# simpleBot.net
KiCad netlist of a schematic drawn in EAGLE
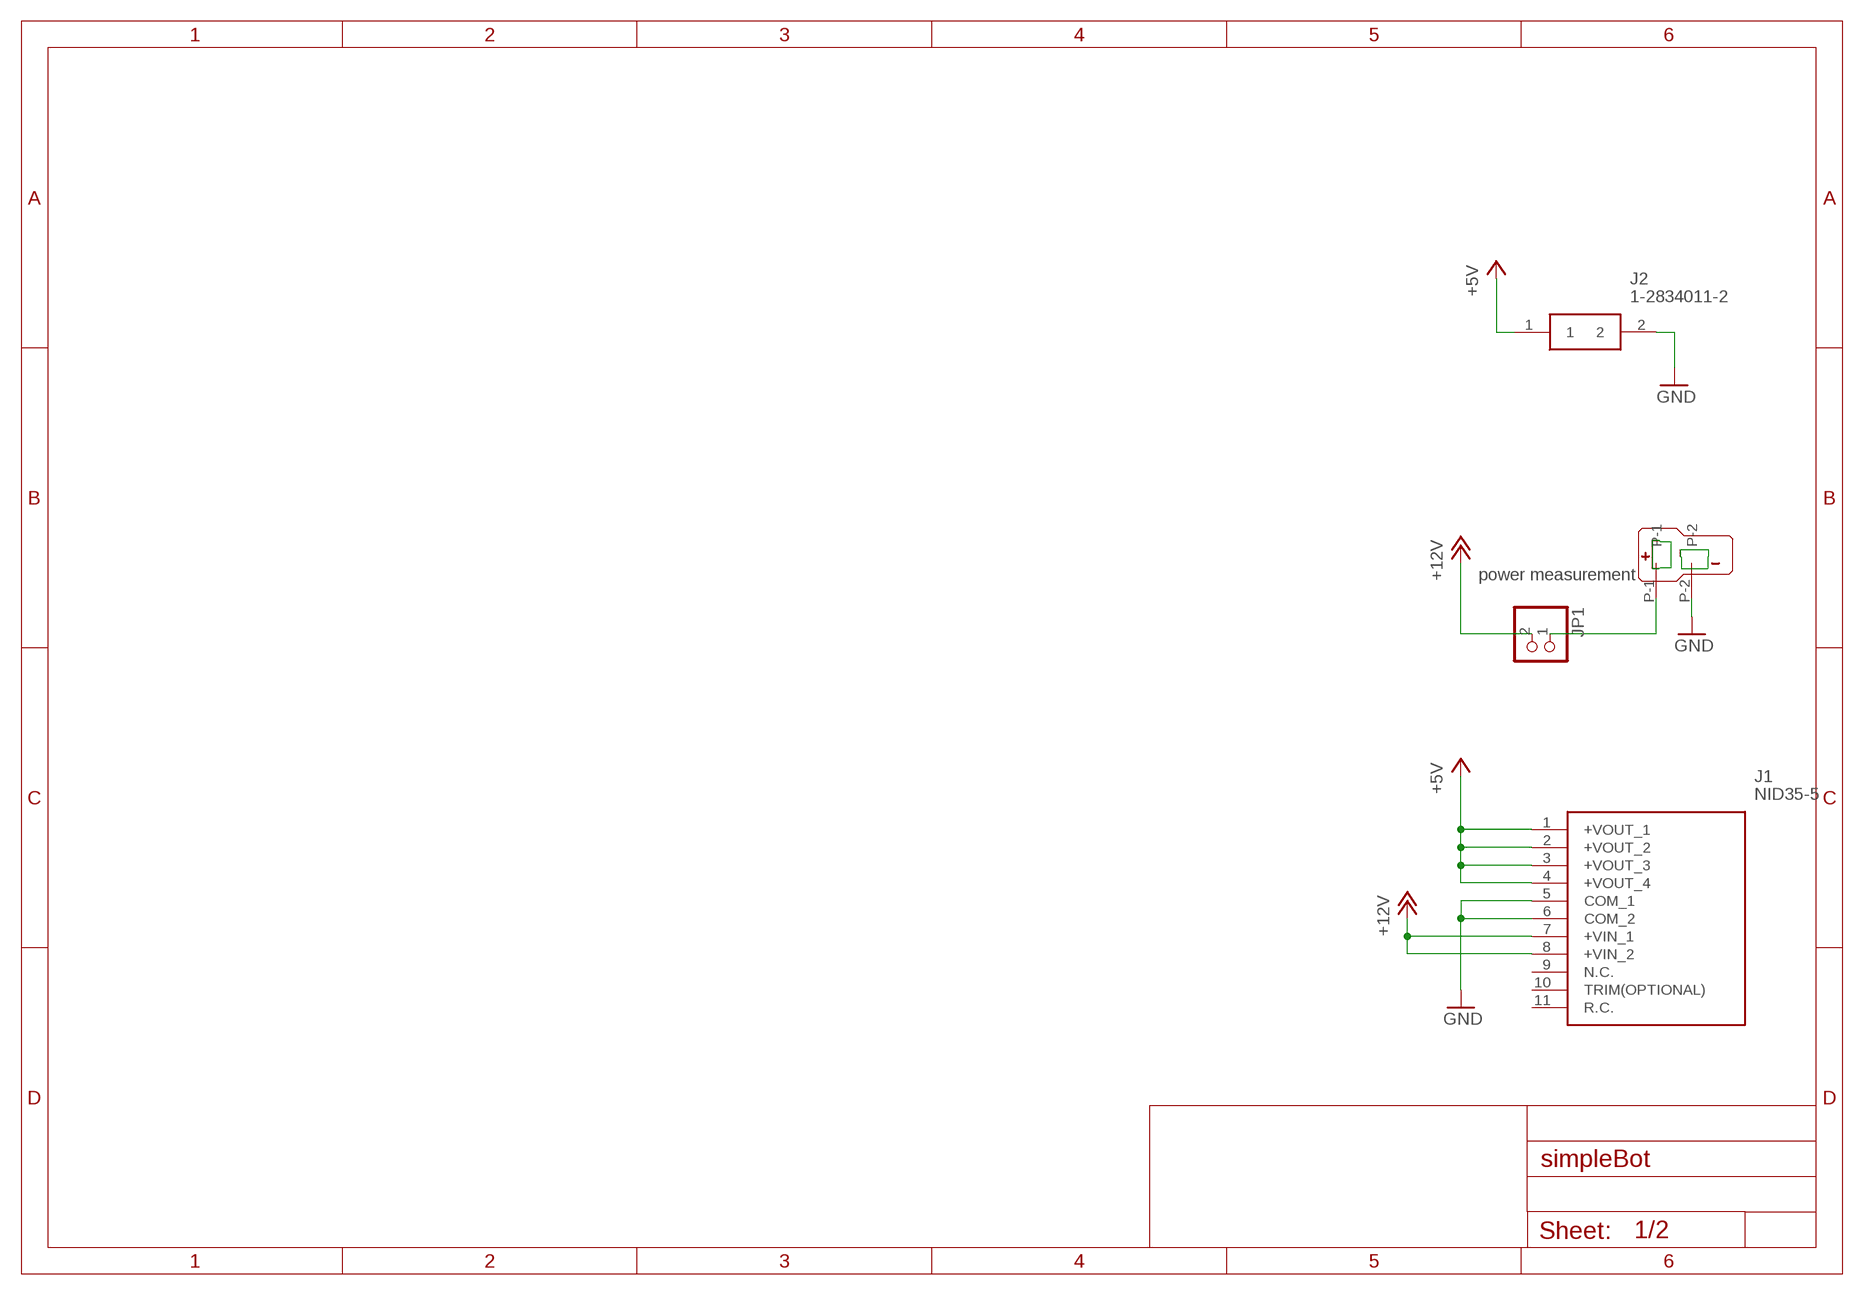
[diagram p0: schematic, sheet 1]
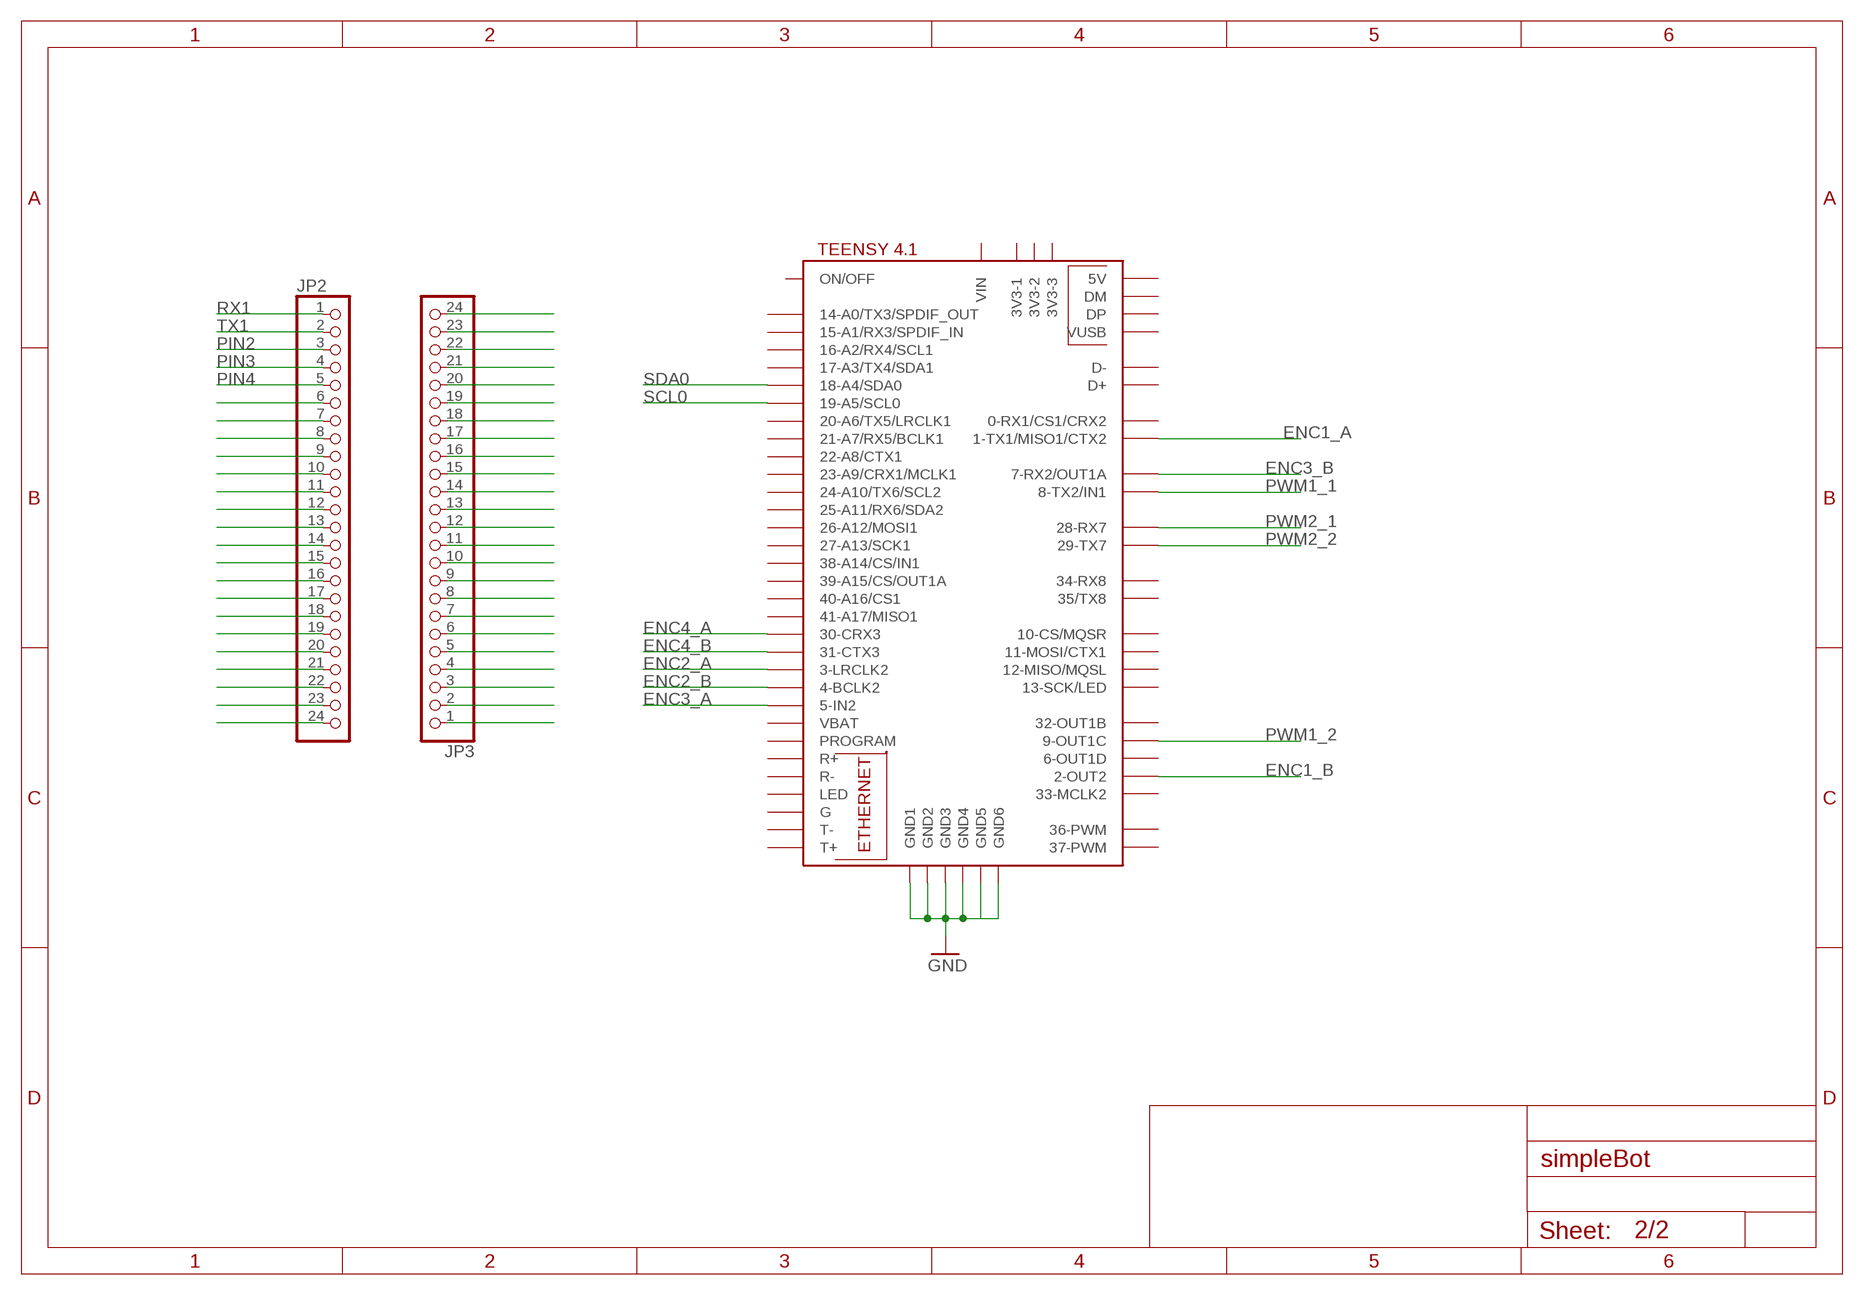
[diagram p1: schematic, sheet 2]

(export (version "E")
  (design (tool "Eeschema 10.0.6"))
  (components
    (comp (ref "JP2")
      (value "PINHD-1X24")
      (footprint "eagle-import:1X24")
      (libsource (lib "eagle-import") (part "PINHD-1X24"))
    )
    (comp (ref "JP3")
      (value "PINHD-1X24")
      (footprint "eagle-import:1X24")
      (libsource (lib "eagle-import") (part "PINHD-1X24"))
    )
    (comp (ref "U$1")
      (value "TEENSY41")
      (footprint "eagle-import:TEENSY41")
      (libsource (lib "eagle-import") (part "TEENSY41"))
    )
    (comp (ref "J1")
      (value "NID35-5")
      (footprint "eagle-import:NID355")
      (libsource (lib "eagle-import") (part "NID35-5"))
    )
    (comp (ref "J2")
      (value "1-2834011-2")
      (footprint "eagle-import:128340112")
      (fields (field (name "RS_PART_NUMBER") "1649131"))
      (libsource (lib "eagle-import") (part "1-2834011-2"))
    )
    (comp (ref "JP1")
      (value "PINHD-1X2")
      (footprint "eagle-import:1X02")
      (libsource (lib "eagle-import") (part "PINHD-1X2"))
    )
    (comp (ref "U$2")
      (value "T-PLUG_CONNECTOR")
      (footprint "eagle-import:T_PLUG_CONNECTOR")
      (libsource (lib "eagle-import") (part "T-PLUG_CONNECTOR"))
    )
  )
  (nets
    (net (code "1") (name "+5V") (class "Default")
      (node (ref "J1") (pin "1") (pinfunction "+VOUT_1_1") (pintype "bidirectional"))
      (node (ref "J1") (pin "2") (pinfunction "+VOUT_2_2") (pintype "bidirectional"))
      (node (ref "J1") (pin "3") (pinfunction "+VOUT_3_3") (pintype "bidirectional"))
      (node (ref "J1") (pin "4") (pinfunction "+VOUT_4_4") (pintype "bidirectional"))
      (node (ref "J2") (pin "1") (pinfunction "1_1") (pintype "bidirectional"))
    )
    (net (code "2") (name "+12V") (class "Default")
      (node (ref "J1") (pin "7") (pinfunction "+VIN_1_7") (pintype "bidirectional"))
      (node (ref "J1") (pin "8") (pinfunction "+VIN_2_8") (pintype "bidirectional"))
      (node (ref "JP1") (pin "2") (pinfunction "2_2") (pintype "passive"))
    )
    (net (code "3") (name "ENC1_A") (class "Default")
      (node (ref "U$1") (pin "1-TX1/MISO1/CTX2") (pinfunction "1-TX1/MISO1/CTX2_1-TX1/MISO1/CTX2") (pintype "bidirectional"))
    )
    (net (code "4") (name "ENC1_B") (class "Default")
      (node (ref "U$1") (pin "2-OUT2") (pinfunction "2-OUT2_2-OUT2") (pintype "bidirectional"))
    )
    (net (code "5") (name "ENC2_A") (class "Default")
      (node (ref "U$1") (pin "3-LRCLK2") (pinfunction "3-LRCLK2_3-LRCLK2") (pintype "bidirectional"))
    )
    (net (code "6") (name "ENC2_B") (class "Default")
      (node (ref "U$1") (pin "4-BCLK2") (pinfunction "4-BCLK2_4-BCLK2") (pintype "bidirectional"))
    )
    (net (code "7") (name "ENC3_A") (class "Default")
      (node (ref "U$1") (pin "5-IN2") (pinfunction "5-IN2_5-IN2") (pintype "bidirectional"))
    )
    (net (code "8") (name "ENC3_B") (class "Default")
      (node (ref "U$1") (pin "7-RX2/OUT1A") (pinfunction "7-RX2/OUT1A_7-RX2/OUT1A") (pintype "bidirectional"))
    )
    (net (code "9") (name "ENC4_A") (class "Default")
      (node (ref "U$1") (pin "30-CRX3") (pinfunction "30-CRX3_30-CRX3") (pintype "bidirectional"))
    )
    (net (code "10") (name "ENC4_B") (class "Default")
      (node (ref "U$1") (pin "31-CTX3") (pinfunction "31-CTX3_31-CTX3") (pintype "bidirectional"))
    )
    (net (code "11") (name "GND") (class "Default")
      (node (ref "J1") (pin "5") (pinfunction "COM_1_5") (pintype "bidirectional"))
      (node (ref "J1") (pin "6") (pinfunction "COM_2_6") (pintype "bidirectional"))
      (node (ref "J2") (pin "2") (pinfunction "2_2") (pintype "bidirectional"))
      (node (ref "U$1") (pin "GND1") (pinfunction "GND1_GND1") (pintype "bidirectional"))
      (node (ref "U$1") (pin "GND2") (pinfunction "GND2_GND2") (pintype "bidirectional"))
      (node (ref "U$1") (pin "GND3") (pinfunction "GND3_GND3") (pintype "bidirectional"))
      (node (ref "U$1") (pin "GND4") (pinfunction "GND4_GND4") (pintype "bidirectional"))
      (node (ref "U$1") (pin "GND5") (pinfunction "GND5_GND5") (pintype "bidirectional"))
      (node (ref "U$1") (pin "GND6") (pinfunction "GND6_GND6") (pintype "bidirectional"))
      (node (ref "U$2") (pin "P-2") (pinfunction "P-2_P-2") (pintype "passive"))
    )
    (net (code "12") (name "Net-(JP1-Pad1)") (class "Default")
      (node (ref "JP1") (pin "1") (pinfunction "1_1") (pintype "passive"))
      (node (ref "U$2") (pin "P-1") (pinfunction "P-1_P-1") (pintype "passive"))
    )
    (net (code "13") (name "PIN2") (class "Default")
      (node (ref "JP2") (pin "3") (pinfunction "3_3") (pintype "passive"))
    )
    (net (code "14") (name "PIN3") (class "Default")
      (node (ref "JP2") (pin "4") (pinfunction "4_4") (pintype "passive"))
    )
    (net (code "15") (name "PIN4") (class "Default")
      (node (ref "JP2") (pin "5") (pinfunction "5_5") (pintype "passive"))
    )
    (net (code "16") (name "PWM1_1") (class "Default")
      (node (ref "U$1") (pin "8-TX2/IN1") (pinfunction "8-TX2/IN1_8-TX2/IN1") (pintype "bidirectional"))
    )
    (net (code "17") (name "PWM1_2") (class "Default")
      (node (ref "U$1") (pin "9-OUT1C") (pinfunction "9-OUT1C_9-OUT1C") (pintype "bidirectional"))
    )
    (net (code "18") (name "PWM2_1") (class "Default")
      (node (ref "U$1") (pin "28-RX7") (pinfunction "28-RX7_28-RX7") (pintype "bidirectional"))
    )
    (net (code "19") (name "PWM2_2") (class "Default")
      (node (ref "U$1") (pin "29-TX7") (pinfunction "29-TX7_29-TX7") (pintype "bidirectional"))
    )
    (net (code "20") (name "RX1") (class "Default")
      (node (ref "JP2") (pin "1") (pinfunction "1_1") (pintype "passive"))
    )
    (net (code "21") (name "SCL0") (class "Default")
      (node (ref "U$1") (pin "19-A5/SCL0") (pinfunction "19-A5/SCL0_19-A5/SCL0") (pintype "bidirectional"))
    )
    (net (code "22") (name "SDA0") (class "Default")
      (node (ref "U$1") (pin "18-A4/SDA0") (pinfunction "18-A4/SDA0_18-A4/SDA0") (pintype "bidirectional"))
    )
    (net (code "23") (name "TX1") (class "Default")
      (node (ref "JP2") (pin "2") (pinfunction "2_2") (pintype "passive"))
    )
    (net (code "24") (name "unconnected-(J1-N.C.-Pad9)") (class "Default")
      (node (ref "J1") (pin "9") (pinfunction "N.C._9") (pintype "no_connect"))
    )
    (net (code "25") (name "unconnected-(J1-R.C.-Pad11)") (class "Default")
      (node (ref "J1") (pin "11") (pinfunction "R.C._11") (pintype "bidirectional"))
    )
    (net (code "26") (name "unconnected-(J1-TRIM(OPTIONAL)-Pad10)") (class "Default")
      (node (ref "J1") (pin "10") (pinfunction "TRIM(OPTIONAL)_10") (pintype "bidirectional"))
    )
    (net (code "27") (name "unconnected-(JP2-Pad6)") (class "Default")
      (node (ref "JP2") (pin "6") (pinfunction "6_6") (pintype "passive"))
    )
    (net (code "28") (name "unconnected-(JP2-Pad7)") (class "Default")
      (node (ref "JP2") (pin "7") (pinfunction "7_7") (pintype "passive"))
    )
    (net (code "29") (name "unconnected-(JP2-Pad8)") (class "Default")
      (node (ref "JP2") (pin "8") (pinfunction "8_8") (pintype "passive"))
    )
    (net (code "30") (name "unconnected-(JP2-Pad9)") (class "Default")
      (node (ref "JP2") (pin "9") (pinfunction "9_9") (pintype "passive"))
    )
    (net (code "31") (name "unconnected-(JP2-Pad10)") (class "Default")
      (node (ref "JP2") (pin "10") (pinfunction "10_10") (pintype "passive"))
    )
    (net (code "32") (name "unconnected-(JP2-Pad11)") (class "Default")
      (node (ref "JP2") (pin "11") (pinfunction "11_11") (pintype "passive"))
    )
    (net (code "33") (name "unconnected-(JP2-Pad12)") (class "Default")
      (node (ref "JP2") (pin "12") (pinfunction "12_12") (pintype "passive"))
    )
    (net (code "34") (name "unconnected-(JP2-Pad13)") (class "Default")
      (node (ref "JP2") (pin "13") (pinfunction "13_13") (pintype "passive"))
    )
    (net (code "35") (name "unconnected-(JP2-Pad14)") (class "Default")
      (node (ref "JP2") (pin "14") (pinfunction "14_14") (pintype "passive"))
    )
    (net (code "36") (name "unconnected-(JP2-Pad15)") (class "Default")
      (node (ref "JP2") (pin "15") (pinfunction "15_15") (pintype "passive"))
    )
    (net (code "37") (name "unconnected-(JP2-Pad16)") (class "Default")
      (node (ref "JP2") (pin "16") (pinfunction "16_16") (pintype "passive"))
    )
    (net (code "38") (name "unconnected-(JP2-Pad17)") (class "Default")
      (node (ref "JP2") (pin "17") (pinfunction "17_17") (pintype "passive"))
    )
    (net (code "39") (name "unconnected-(JP2-Pad18)") (class "Default")
      (node (ref "JP2") (pin "18") (pinfunction "18_18") (pintype "passive"))
    )
    (net (code "40") (name "unconnected-(JP2-Pad19)") (class "Default")
      (node (ref "JP2") (pin "19") (pinfunction "19_19") (pintype "passive"))
    )
    (net (code "41") (name "unconnected-(JP2-Pad20)") (class "Default")
      (node (ref "JP2") (pin "20") (pinfunction "20_20") (pintype "passive"))
    )
    (net (code "42") (name "unconnected-(JP2-Pad21)") (class "Default")
      (node (ref "JP2") (pin "21") (pinfunction "21_21") (pintype "passive"))
    )
    (net (code "43") (name "unconnected-(JP2-Pad22)") (class "Default")
      (node (ref "JP2") (pin "22") (pinfunction "22_22") (pintype "passive"))
    )
    (net (code "44") (name "unconnected-(JP2-Pad23)") (class "Default")
      (node (ref "JP2") (pin "23") (pinfunction "23_23") (pintype "passive"))
    )
    (net (code "45") (name "unconnected-(JP2-Pad24)") (class "Default")
      (node (ref "JP2") (pin "24") (pinfunction "24_24") (pintype "passive"))
    )
    (net (code "46") (name "unconnected-(JP3-Pad1)") (class "Default")
      (node (ref "JP3") (pin "1") (pinfunction "1_1") (pintype "passive"))
    )
    (net (code "47") (name "unconnected-(JP3-Pad2)") (class "Default")
      (node (ref "JP3") (pin "2") (pinfunction "2_2") (pintype "passive"))
    )
    (net (code "48") (name "unconnected-(JP3-Pad3)") (class "Default")
      (node (ref "JP3") (pin "3") (pinfunction "3_3") (pintype "passive"))
    )
    (net (code "49") (name "unconnected-(JP3-Pad4)") (class "Default")
      (node (ref "JP3") (pin "4") (pinfunction "4_4") (pintype "passive"))
    )
    (net (code "50") (name "unconnected-(JP3-Pad5)") (class "Default")
      (node (ref "JP3") (pin "5") (pinfunction "5_5") (pintype "passive"))
    )
    (net (code "51") (name "unconnected-(JP3-Pad6)") (class "Default")
      (node (ref "JP3") (pin "6") (pinfunction "6_6") (pintype "passive"))
    )
    (net (code "52") (name "unconnected-(JP3-Pad7)") (class "Default")
      (node (ref "JP3") (pin "7") (pinfunction "7_7") (pintype "passive"))
    )
    (net (code "53") (name "unconnected-(JP3-Pad8)") (class "Default")
      (node (ref "JP3") (pin "8") (pinfunction "8_8") (pintype "passive"))
    )
    (net (code "54") (name "unconnected-(JP3-Pad9)") (class "Default")
      (node (ref "JP3") (pin "9") (pinfunction "9_9") (pintype "passive"))
    )
    (net (code "55") (name "unconnected-(JP3-Pad10)") (class "Default")
      (node (ref "JP3") (pin "10") (pinfunction "10_10") (pintype "passive"))
    )
    (net (code "56") (name "unconnected-(JP3-Pad11)") (class "Default")
      (node (ref "JP3") (pin "11") (pinfunction "11_11") (pintype "passive"))
    )
    (net (code "57") (name "unconnected-(JP3-Pad12)") (class "Default")
      (node (ref "JP3") (pin "12") (pinfunction "12_12") (pintype "passive"))
    )
    (net (code "58") (name "unconnected-(JP3-Pad13)") (class "Default")
      (node (ref "JP3") (pin "13") (pinfunction "13_13") (pintype "passive"))
    )
    (net (code "59") (name "unconnected-(JP3-Pad14)") (class "Default")
      (node (ref "JP3") (pin "14") (pinfunction "14_14") (pintype "passive"))
    )
    (net (code "60") (name "unconnected-(JP3-Pad15)") (class "Default")
      (node (ref "JP3") (pin "15") (pinfunction "15_15") (pintype "passive"))
    )
    (net (code "61") (name "unconnected-(JP3-Pad16)") (class "Default")
      (node (ref "JP3") (pin "16") (pinfunction "16_16") (pintype "passive"))
    )
    (net (code "62") (name "unconnected-(JP3-Pad17)") (class "Default")
      (node (ref "JP3") (pin "17") (pinfunction "17_17") (pintype "passive"))
    )
    (net (code "63") (name "unconnected-(JP3-Pad18)") (class "Default")
      (node (ref "JP3") (pin "18") (pinfunction "18_18") (pintype "passive"))
    )
    (net (code "64") (name "unconnected-(JP3-Pad19)") (class "Default")
      (node (ref "JP3") (pin "19") (pinfunction "19_19") (pintype "passive"))
    )
    (net (code "65") (name "unconnected-(JP3-Pad20)") (class "Default")
      (node (ref "JP3") (pin "20") (pinfunction "20_20") (pintype "passive"))
    )
    (net (code "66") (name "unconnected-(JP3-Pad21)") (class "Default")
      (node (ref "JP3") (pin "21") (pinfunction "21_21") (pintype "passive"))
    )
    (net (code "67") (name "unconnected-(JP3-Pad22)") (class "Default")
      (node (ref "JP3") (pin "22") (pinfunction "22_22") (pintype "passive"))
    )
    (net (code "68") (name "unconnected-(JP3-Pad23)") (class "Default")
      (node (ref "JP3") (pin "23") (pinfunction "23_23") (pintype "passive"))
    )
    (net (code "69") (name "unconnected-(JP3-Pad24)") (class "Default")
      (node (ref "JP3") (pin "24") (pinfunction "24_24") (pintype "passive"))
    )
    (net (code "70") (name "unconnected-(U$1-5V-Pad+5V)") (class "Default")
      (node (ref "U$1") (pin "+5V") (pinfunction "5V_+5V") (pintype "bidirectional"))
    )
    (net (code "71") (name "unconnected-(U$1-10-CS{slash}MQSR-Pad10-CS\\MQSR)") (class "Default")
      (node (ref "U$1") (pin "10-CS\\MQSR") (pinfunction "10-CS/MQSR_10-CS\\MQSR") (pintype "bidirectional"))
    )
    (net (code "72") (name "unconnected-(U$1-35{slash}TX8-Pad35-TX8)") (class "Default")
      (node (ref "U$1") (pin "35-TX8") (pinfunction "35/TX8_35-TX8") (pintype "bidirectional"))
    )
    (net (code "73") (name "unconnected-(U$1-Pad0-RX1{slash}CS1{slash}CRX2)") (class "Default")
      (node (ref "U$1") (pin "0-RX1/CS1/CRX2") (pinfunction "0-RX1/CS1/CRX2_0-RX1/CS1/CRX2") (pintype "bidirectional"))
    )
    (net (code "74") (name "unconnected-(U$1-Pad3V3-1)") (class "Default")
      (node (ref "U$1") (pin "3V3-1") (pinfunction "3V3-1_3V3-1") (pintype "bidirectional"))
    )
    (net (code "75") (name "unconnected-(U$1-Pad3V3-2)") (class "Default")
      (node (ref "U$1") (pin "3V3-2") (pinfunction "3V3-2_3V3-2") (pintype "bidirectional"))
    )
    (net (code "76") (name "unconnected-(U$1-Pad3V3-3)") (class "Default")
      (node (ref "U$1") (pin "3V3-3") (pinfunction "3V3-3_3V3-3") (pintype "bidirectional"))
    )
    (net (code "77") (name "unconnected-(U$1-Pad6-OUT1D)") (class "Default")
      (node (ref "U$1") (pin "6-OUT1D") (pinfunction "6-OUT1D_6-OUT1D") (pintype "bidirectional"))
    )
    (net (code "78") (name "unconnected-(U$1-Pad11-MOSI{slash}CTX1)") (class "Default")
      (node (ref "U$1") (pin "11-MOSI/CTX1") (pinfunction "11-MOSI/CTX1_11-MOSI/CTX1") (pintype "bidirectional"))
    )
    (net (code "79") (name "unconnected-(U$1-Pad12-MISO{slash}MQSL)") (class "Default")
      (node (ref "U$1") (pin "12-MISO/MQSL") (pinfunction "12-MISO/MQSL_12-MISO/MQSL") (pintype "bidirectional"))
    )
    (net (code "80") (name "unconnected-(U$1-Pad13-SCK{slash}LED)") (class "Default")
      (node (ref "U$1") (pin "13-SCK/LED") (pinfunction "13-SCK/LED_13-SCK/LED") (pintype "bidirectional"))
    )
    (net (code "81") (name "unconnected-(U$1-Pad14-A0{slash}TX3{slash}SPDIF_OUT)") (class "Default")
      (node (ref "U$1") (pin "14-A0/TX3/SPDIF_OUT") (pinfunction "14-A0/TX3/SPDIF_OUT_14-A0/TX3/SPDIF_OUT") (pintype "bidirectional"))
    )
    (net (code "82") (name "unconnected-(U$1-Pad15-A1{slash}RX3{slash}SPDIF_IN)") (class "Default")
      (node (ref "U$1") (pin "15-A1/RX3/SPDIF_IN") (pinfunction "15-A1/RX3/SPDIF_IN_15-A1/RX3/SPDIF_IN") (pintype "bidirectional"))
    )
    (net (code "83") (name "unconnected-(U$1-Pad16-A2{slash}RX4{slash}SCL1)") (class "Default")
      (node (ref "U$1") (pin "16-A2/RX4/SCL1") (pinfunction "16-A2/RX4/SCL1_16-A2/RX4/SCL1") (pintype "bidirectional"))
    )
    (net (code "84") (name "unconnected-(U$1-Pad17-A3{slash}TX4{slash}SDA1)") (class "Default")
      (node (ref "U$1") (pin "17-A3/TX4/SDA1") (pinfunction "17-A3/TX4/SDA1_17-A3/TX4/SDA1") (pintype "bidirectional"))
    )
    (net (code "85") (name "unconnected-(U$1-Pad20-A6{slash}TX5{slash}LRCLK1)") (class "Default")
      (node (ref "U$1") (pin "20-A6/TX5/LRCLK1") (pinfunction "20-A6/TX5/LRCLK1_20-A6/TX5/LRCLK1") (pintype "bidirectional"))
    )
    (net (code "86") (name "unconnected-(U$1-Pad21-A7{slash}RX5{slash}BCLK1)") (class "Default")
      (node (ref "U$1") (pin "21-A7/RX5/BCLK1") (pinfunction "21-A7/RX5/BCLK1_21-A7/RX5/BCLK1") (pintype "bidirectional"))
    )
    (net (code "87") (name "unconnected-(U$1-Pad22-A8{slash}CTX1)") (class "Default")
      (node (ref "U$1") (pin "22-A8/CTX1") (pinfunction "22-A8/CTX1_22-A8/CTX1") (pintype "bidirectional"))
    )
    (net (code "88") (name "unconnected-(U$1-Pad23-A9{slash}CRX1{slash}MCLK1)") (class "Default")
      (node (ref "U$1") (pin "23-A9/CRX1/MCLK1") (pinfunction "23-A9/CRX1/MCLK1_23-A9/CRX1/MCLK1") (pintype "bidirectional"))
    )
    (net (code "89") (name "unconnected-(U$1-Pad24-A10{slash}TX6{slash}SCL2)") (class "Default")
      (node (ref "U$1") (pin "24-A10/TX6/SCL2") (pinfunction "24-A10/TX6/SCL2_24-A10/TX6/SCL2") (pintype "bidirectional"))
    )
    (net (code "90") (name "unconnected-(U$1-Pad25-A11{slash}RX6{slash}SDA2)") (class "Default")
      (node (ref "U$1") (pin "25-A11/RX6/SDA2") (pinfunction "25-A11/RX6/SDA2_25-A11/RX6/SDA2") (pintype "bidirectional"))
    )
    (net (code "91") (name "unconnected-(U$1-Pad26-A12{slash}MOSI1)") (class "Default")
      (node (ref "U$1") (pin "26-A12/MOSI1") (pinfunction "26-A12/MOSI1_26-A12/MOSI1") (pintype "bidirectional"))
    )
    (net (code "92") (name "unconnected-(U$1-Pad27-A13{slash}SCK1)") (class "Default")
      (node (ref "U$1") (pin "27-A13/SCK1") (pinfunction "27-A13/SCK1_27-A13/SCK1") (pintype "bidirectional"))
    )
    (net (code "93") (name "unconnected-(U$1-Pad32-OUT1B)") (class "Default")
      (node (ref "U$1") (pin "32-OUT1B") (pinfunction "32-OUT1B_32-OUT1B") (pintype "bidirectional"))
    )
    (net (code "94") (name "unconnected-(U$1-Pad33-MCLK2)") (class "Default")
      (node (ref "U$1") (pin "33-MCLK2") (pinfunction "33-MCLK2_33-MCLK2") (pintype "bidirectional"))
    )
    (net (code "95") (name "unconnected-(U$1-Pad34-RX8)") (class "Default")
      (node (ref "U$1") (pin "34-RX8") (pinfunction "34-RX8_34-RX8") (pintype "bidirectional"))
    )
    (net (code "96") (name "unconnected-(U$1-Pad36-PWM)") (class "Default")
      (node (ref "U$1") (pin "36-PWM") (pinfunction "36-PWM_36-PWM") (pintype "bidirectional"))
    )
    (net (code "97") (name "unconnected-(U$1-Pad37-PWM)") (class "Default")
      (node (ref "U$1") (pin "37-PWM") (pinfunction "37-PWM_37-PWM") (pintype "bidirectional"))
    )
    (net (code "98") (name "unconnected-(U$1-Pad38-A14{slash}CS{slash}IN1)") (class "Default")
      (node (ref "U$1") (pin "38-A14/CS/IN1") (pinfunction "38-A14/CS/IN1_38-A14/CS/IN1") (pintype "bidirectional"))
    )
    (net (code "99") (name "unconnected-(U$1-Pad39-A15{slash}CS{slash}OUT1A)") (class "Default")
      (node (ref "U$1") (pin "39-A15/CS/OUT1A") (pinfunction "39-A15/CS/OUT1A_39-A15/CS/OUT1A") (pintype "bidirectional"))
    )
    (net (code "100") (name "unconnected-(U$1-Pad40-A16{slash}CS1)") (class "Default")
      (node (ref "U$1") (pin "40-A16/CS1") (pinfunction "40-A16/CS1_40-A16/CS1") (pintype "bidirectional"))
    )
    (net (code "101") (name "unconnected-(U$1-Pad41-A17{slash}MISO1)") (class "Default")
      (node (ref "U$1") (pin "41-A17/MISO1") (pinfunction "41-A17/MISO1_41-A17/MISO1") (pintype "bidirectional"))
    )
    (net (code "102") (name "unconnected-(U$1-PadD+)") (class "Default")
      (node (ref "U$1") (pin "D+") (pinfunction "D+_D+") (pintype "bidirectional"))
    )
    (net (code "103") (name "unconnected-(U$1-PadD-)") (class "Default")
      (node (ref "U$1") (pin "D-") (pinfunction "D-_D-") (pintype "bidirectional"))
    )
    (net (code "104") (name "unconnected-(U$1-PadDM)") (class "Default")
      (node (ref "U$1") (pin "DM") (pinfunction "DM_DM") (pintype "bidirectional"))
    )
    (net (code "105") (name "unconnected-(U$1-PadDP)") (class "Default")
      (node (ref "U$1") (pin "DP") (pinfunction "DP_DP") (pintype "bidirectional"))
    )
    (net (code "106") (name "unconnected-(U$1-PadG)") (class "Default")
      (node (ref "U$1") (pin "G") (pinfunction "G_G") (pintype "bidirectional"))
    )
    (net (code "107") (name "unconnected-(U$1-PadLED)") (class "Default")
      (node (ref "U$1") (pin "LED") (pinfunction "LED_LED") (pintype "bidirectional"))
    )
    (net (code "108") (name "unconnected-(U$1-PadON{slash}OFF)") (class "Default")
      (node (ref "U$1") (pin "ON/OFF") (pinfunction "ON/OFF_ON/OFF") (pintype "bidirectional"))
    )
    (net (code "109") (name "unconnected-(U$1-PadPROGRAM)") (class "Default")
      (node (ref "U$1") (pin "PROGRAM") (pinfunction "PROGRAM_PROGRAM") (pintype "bidirectional"))
    )
    (net (code "110") (name "unconnected-(U$1-PadR+)") (class "Default")
      (node (ref "U$1") (pin "R+") (pinfunction "R+_R+") (pintype "bidirectional"))
    )
    (net (code "111") (name "unconnected-(U$1-PadR-)") (class "Default")
      (node (ref "U$1") (pin "R-") (pinfunction "R-_R-") (pintype "bidirectional"))
    )
    (net (code "112") (name "unconnected-(U$1-PadT+)") (class "Default")
      (node (ref "U$1") (pin "T+") (pinfunction "T+_T+") (pintype "bidirectional"))
    )
    (net (code "113") (name "unconnected-(U$1-PadT-)") (class "Default")
      (node (ref "U$1") (pin "T-") (pinfunction "T-_T-") (pintype "bidirectional"))
    )
    (net (code "114") (name "unconnected-(U$1-PadVBAT)") (class "Default")
      (node (ref "U$1") (pin "VBAT") (pinfunction "VBAT_VBAT") (pintype "bidirectional"))
    )
    (net (code "115") (name "unconnected-(U$1-PadVIN)") (class "Default")
      (node (ref "U$1") (pin "VIN") (pinfunction "VIN_VIN") (pintype "bidirectional"))
    )
    (net (code "116") (name "unconnected-(U$1-PadVUSB)") (class "Default")
      (node (ref "U$1") (pin "VUSB") (pinfunction "VUSB_VUSB") (pintype "bidirectional"))
    )
  )
)
